# BRZ_BATT_MGR.net
KiCad netlist of a schematic drawn in Altium Designer
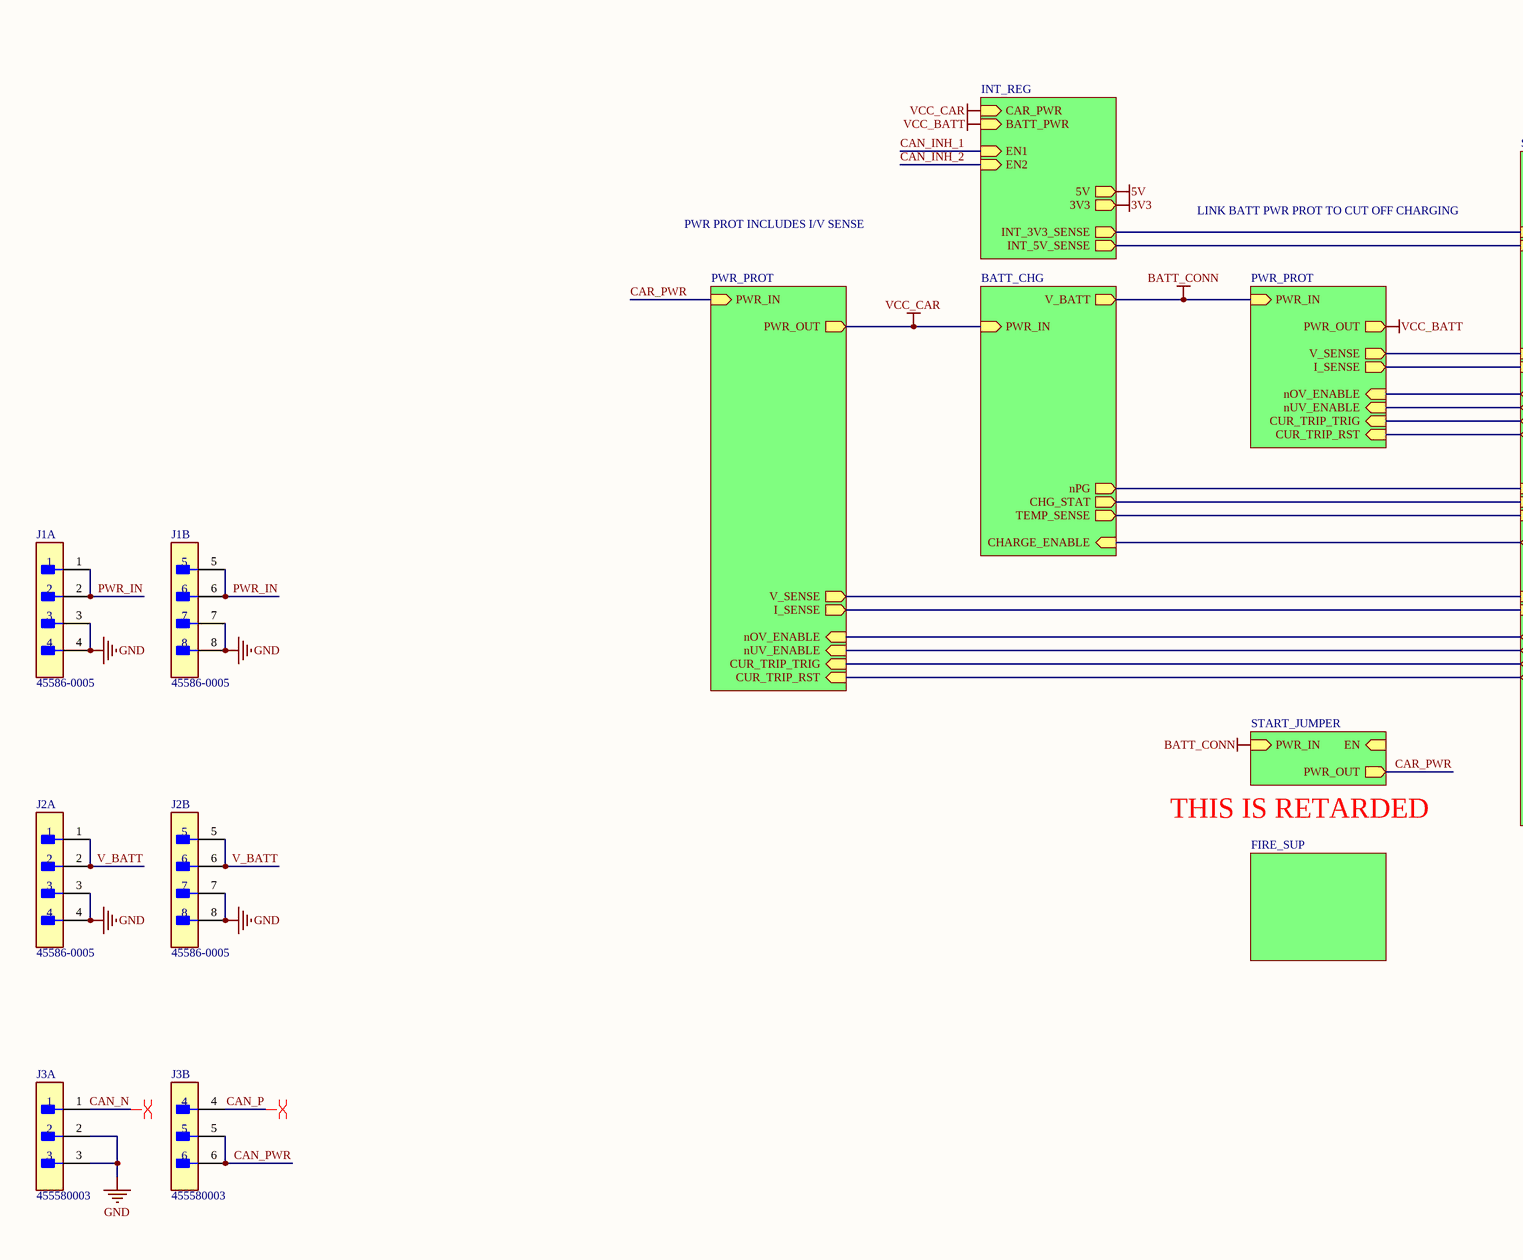
[diagram p0: BRZ_BATT_MGR.SchDoc, left]
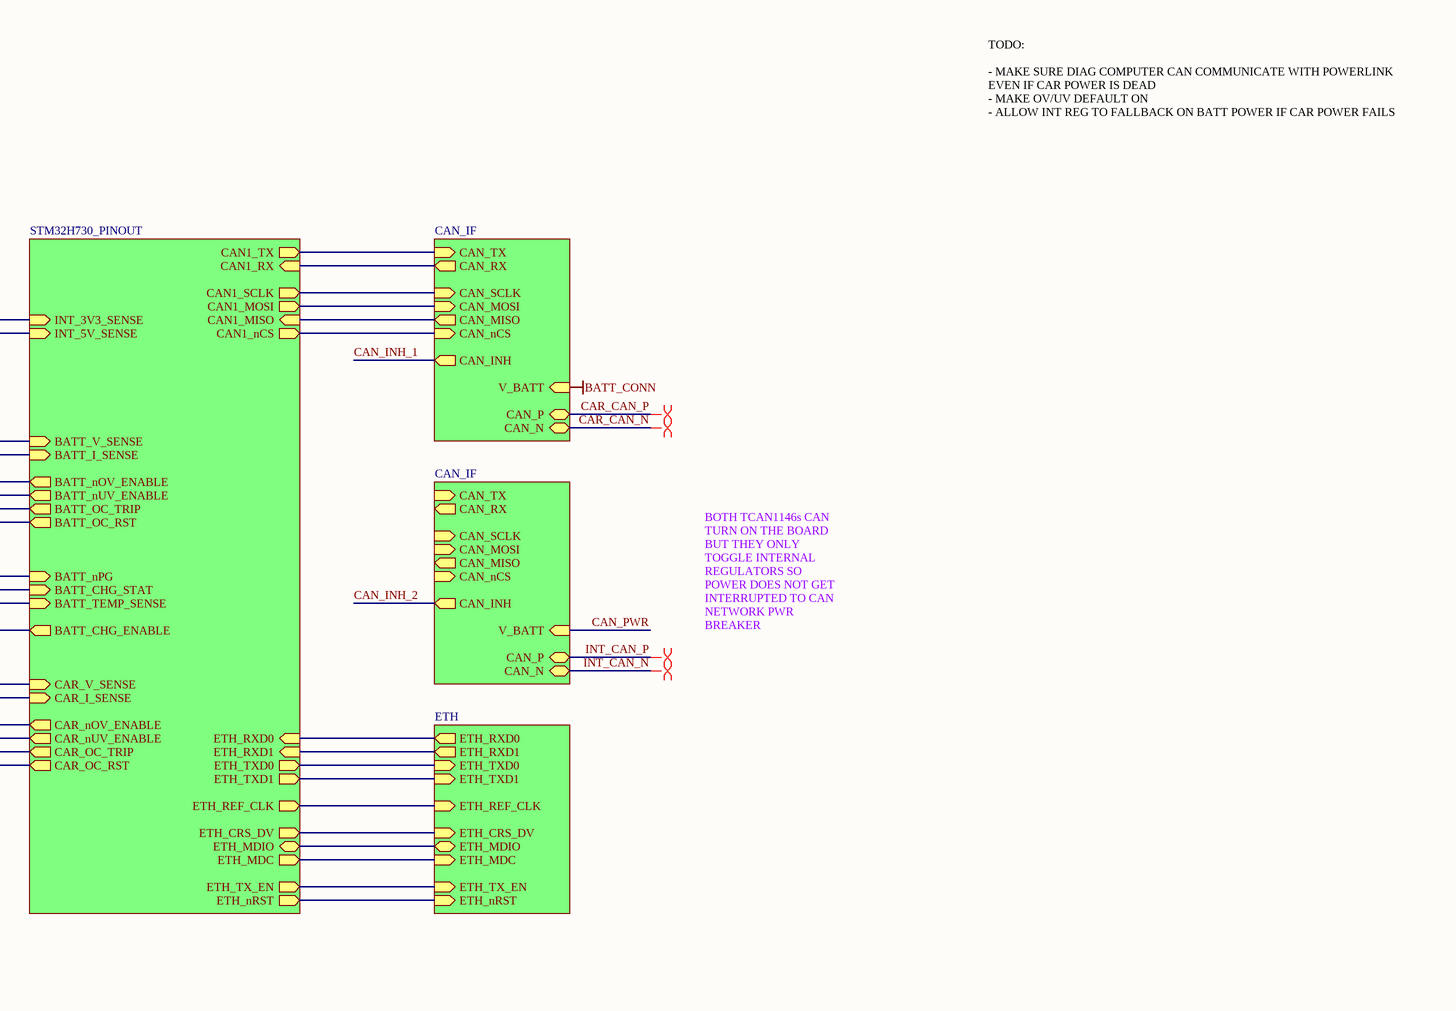
[diagram p1: BRZ_BATT_MGR.SchDoc, right]

(export (version "E")
  (design (tool "Eeschema 10.0.6"))
  (components
    (comp (ref "J1")
      (value "45586-0005")
      (footprint "FP-45586-0005-MFG")
      (description "CONN HEADER R/A 8POS 4.2MM")
      (libsource (lib "Altium Content Vault") (part "85438c39ca9ef07d43bb2e97c52bc44"))
    )
    (comp (ref "J2")
      (value "45586-0005")
      (footprint "FP-45586-0005-MFG")
      (description "CONN HEADER R/A 8POS 4.2MM")
      (libsource (lib "Altium Content Vault") (part "85438c39ca9ef07d43bb2e97c52bc44"))
    )
    (comp (ref "J3")
      (value "455580003")
      (footprint "FP-455580003-MFG")
      (description "CONN HEADER R/A 6POS 4.2MM")
      (fields
        (field (name "OCTOPART") "https://octopart.com/45558-0003-molex-7672845")
        (field (name "MANUFACTURER") "Molex")
      )
      (libsource (lib "Altium Content Vault") (part "bb9cbdb24149a20ba329b4e86909569"))
    )
  )
  (nets
    (net (code "15") (name "/CAN_N") (class "Default")
      (node (ref "J3") (pin "1") (pinfunction "1_1") (pintype "passive"))
    )
    (net (code "16") (name "/CAN_P") (class "Default")
      (node (ref "J3") (pin "4") (pinfunction "4_4") (pintype "passive"))
    )
    (net (code "17") (name "/CAN_PWR") (class "Default")
      (node (ref "J3") (pin "5") (pinfunction "5_5") (pintype "passive"))
      (node (ref "J3") (pin "6") (pinfunction "6_6") (pintype "passive"))
    )
    (net (code "48") (name "/PWR_IN") (class "Default")
      (node (ref "J1") (pin "1") (pinfunction "1_1") (pintype "passive"))
      (node (ref "J1") (pin "2") (pinfunction "2_2") (pintype "passive"))
      (node (ref "J1") (pin "5") (pinfunction "5_5") (pintype "passive"))
      (node (ref "J1") (pin "6") (pinfunction "6_6") (pintype "passive"))
    )
    (net (code "50") (name "/V_BATT") (class "Default")
      (node (ref "J2") (pin "1") (pinfunction "1_1") (pintype "passive"))
      (node (ref "J2") (pin "2") (pinfunction "2_2") (pintype "passive"))
      (node (ref "J2") (pin "5") (pinfunction "5_5") (pintype "passive"))
      (node (ref "J2") (pin "6") (pinfunction "6_6") (pintype "passive"))
    )
    (net (code "57") (name "GND") (class "Default")
      (node (ref "J1") (pin "3") (pinfunction "3_3") (pintype "passive"))
      (node (ref "J1") (pin "4") (pinfunction "4_4") (pintype "passive"))
      (node (ref "J1") (pin "7") (pinfunction "7_7") (pintype "passive"))
      (node (ref "J1") (pin "8") (pinfunction "8_8") (pintype "passive"))
      (node (ref "J2") (pin "3") (pinfunction "3_3") (pintype "passive"))
      (node (ref "J2") (pin "4") (pinfunction "4_4") (pintype "passive"))
      (node (ref "J2") (pin "7") (pinfunction "7_7") (pintype "passive"))
      (node (ref "J2") (pin "8") (pinfunction "8_8") (pintype "passive"))
      (node (ref "J3") (pin "2") (pinfunction "2_2") (pintype "passive"))
      (node (ref "J3") (pin "3") (pinfunction "3_3") (pintype "passive"))
    )
  )
)
